# OpenModem_Schematic.net
KiCad netlist of a schematic drawn in EAGLE
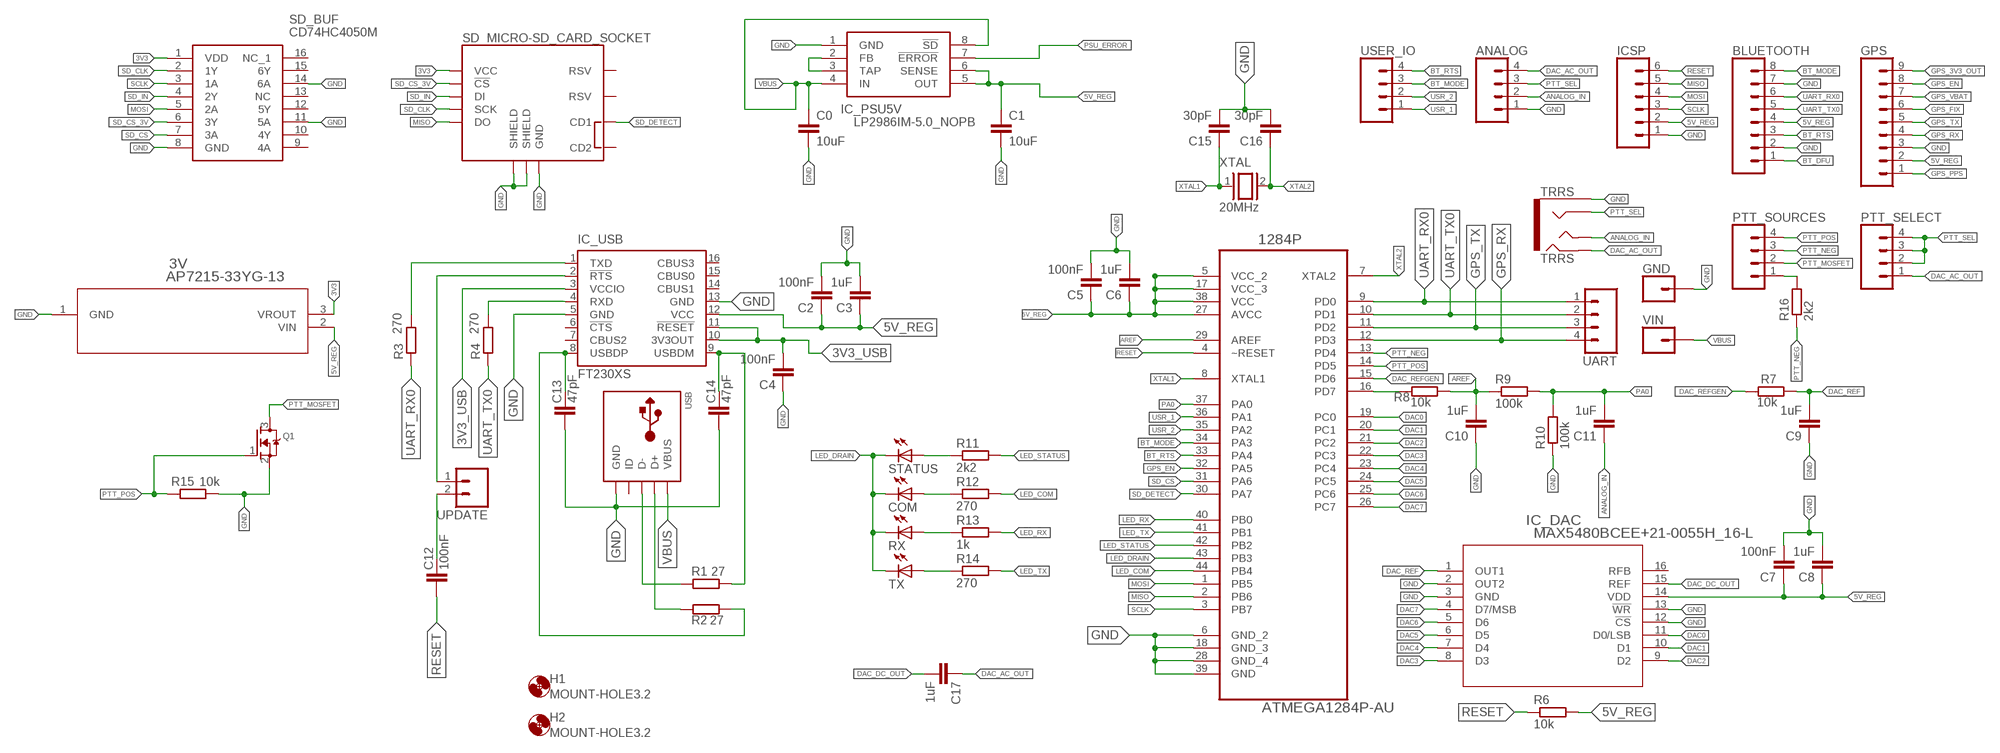
[diagram p0: schematic, sheet 1]

(export (version "E")
  (design (tool "Eeschema 10.0.6"))
  (components
    (comp (ref "3V")
      (value "AP7215-33YG-13")
      (footprint "eagle-import:SOT89-3L")
      (fields (field (name "MANUFACTURER_PART_NUMBER") "AP721533YG13"))
      (libsource (lib "eagle-import") (part "AP7215-33YG-13"))
    )
    (comp (ref "1284P")
      (value "ATMEGA1284P-AU")
      (footprint "eagle-import:QFP80P1200X1200X120-44N")
      (libsource (lib "eagle-import") (part "ATMEGA1284P-AU"))
    )
    (comp (ref "ANALOG")
      (value "CONN_04")
      (footprint "eagle-import:1X04")
      (libsource (lib "eagle-import") (part "CONN_04"))
    )
    (comp (ref "BLUETOOTH")
      (value "CONN_08\"")
      (footprint "eagle-import:1X08")
      (libsource (lib "eagle-import") (part "CONN_08{dblquote}"))
    )
    (comp (ref "C0")
      (value "10uF")
      (footprint "eagle-import:C0805")
      (libsource (lib "eagle-import") (part "C-EUC0805"))
    )
    (comp (ref "C1")
      (value "10uF")
      (footprint "eagle-import:C0805")
      (libsource (lib "eagle-import") (part "C-EUC0805"))
    )
    (comp (ref "C2")
      (value "100nF")
      (footprint "eagle-import:C0603")
      (libsource (lib "eagle-import") (part "C-EUC0603"))
    )
    (comp (ref "C3")
      (value "1uF")
      (footprint "eagle-import:C0603")
      (libsource (lib "eagle-import") (part "C-EUC0603"))
    )
    (comp (ref "C4")
      (value "100nF")
      (footprint "eagle-import:C0603")
      (libsource (lib "eagle-import") (part "C-EUC0603"))
    )
    (comp (ref "C5")
      (value "100nF")
      (footprint "eagle-import:C0603")
      (libsource (lib "eagle-import") (part "C-EUC0603"))
    )
    (comp (ref "C6")
      (value "1uF")
      (footprint "eagle-import:C0603")
      (libsource (lib "eagle-import") (part "C-EUC0603"))
    )
    (comp (ref "C7")
      (value "100nF")
      (footprint "eagle-import:C0603")
      (libsource (lib "eagle-import") (part "C-EUC0603"))
    )
    (comp (ref "C8")
      (value "1uF")
      (footprint "eagle-import:C0603")
      (libsource (lib "eagle-import") (part "C-EUC0603"))
    )
    (comp (ref "C9")
      (value "1uF")
      (footprint "eagle-import:C0603")
      (libsource (lib "eagle-import") (part "C-EUC0603"))
    )
    (comp (ref "C10")
      (value "1uF")
      (footprint "eagle-import:C0603")
      (libsource (lib "eagle-import") (part "C-EUC0603"))
    )
    (comp (ref "C11")
      (value "1uF")
      (footprint "eagle-import:C0603")
      (libsource (lib "eagle-import") (part "C-EUC0603"))
    )
    (comp (ref "C12")
      (value "100nF")
      (footprint "eagle-import:C0603")
      (libsource (lib "eagle-import") (part "C-EUC0603"))
    )
    (comp (ref "C13")
      (value "47pF")
      (footprint "eagle-import:C0603")
      (libsource (lib "eagle-import") (part "C-EUC0603"))
    )
    (comp (ref "C14")
      (value "47pF")
      (footprint "eagle-import:C0603")
      (libsource (lib "eagle-import") (part "C-EUC0603"))
    )
    (comp (ref "C15")
      (value "30pF")
      (footprint "eagle-import:C0603")
      (libsource (lib "eagle-import") (part "C-EUC0603"))
    )
    (comp (ref "C16")
      (value "30pF")
      (footprint "eagle-import:C0603")
      (libsource (lib "eagle-import") (part "C-EUC0603"))
    )
    (comp (ref "C17")
      (value "1uF")
      (footprint "eagle-import:C0603")
      (libsource (lib "eagle-import") (part "C-EUC0603"))
    )
    (comp (ref "COM")
      (value "LEDCHIP-LED0603")
      (footprint "eagle-import:CHIP-LED0603")
      (libsource (lib "eagle-import") (part "LEDCHIP-LED0603"))
    )
    (comp (ref "GND")
      (value "CONN_01")
      (footprint "eagle-import:1X01")
      (libsource (lib "eagle-import") (part "CONN_01"))
    )
    (comp (ref "GPS")
      (value "CONN_09")
      (footprint "eagle-import:1X09")
      (libsource (lib "eagle-import") (part "CONN_09"))
    )
    (comp (ref "H1")
      (value "MOUNT-HOLE3.2")
      (footprint "eagle-import:3,2")
      (libsource (lib "eagle-import") (part "MOUNT-HOLE3.2"))
    )
    (comp (ref "H2")
      (value "MOUNT-HOLE3.2")
      (footprint "eagle-import:3,2")
      (libsource (lib "eagle-import") (part "MOUNT-HOLE3.2"))
    )
    (comp (ref "ICSP")
      (value "CONN_06SILK_FEMALE_PTH")
      (footprint "eagle-import:1X06")
      (libsource (lib "eagle-import") (part "CONN_06SILK_FEMALE_PTH"))
    )
    (comp (ref "IC_DAC")
      (value "MAX5480BCEE+21-0055H_16-L")
      (footprint "eagle-import:21-0055H_16-L")
      (fields (field (name "MANUFACTURER_PART_NUMBER") "MAX5480BCEE+"))
      (libsource (lib "eagle-import") (part "MAX5480BCEE+21-0055H_16-L"))
    )
    (comp (ref "IC_PSU5V")
      (value "LP2986IM-5.0_NOPB")
      (footprint "eagle-import:SOIC127P600X175-8N")
      (fields
        (field (name "MANUFACTURER_PART_NUMBER") "LP2986IM-5.0/NOPB")
        (field (name "MOUSER_PART_NUMBER") "926-2986IM-5.0/NOPB")
      )
      (libsource (lib "eagle-import") (part "LP2986IM-5.0_NOPB"))
    )
    (comp (ref "IC_USB")
      (value "FT230XS")
      (footprint "eagle-import:SSOP16")
      (libsource (lib "eagle-import") (part "FT230XS"))
    )
    (comp (ref "PTT_SELECT")
      (value "CONN_04")
      (footprint "eagle-import:1X04")
      (libsource (lib "eagle-import") (part "CONN_04"))
    )
    (comp (ref "PTT_SOURCES")
      (value "CONN_04")
      (footprint "eagle-import:1X04")
      (libsource (lib "eagle-import") (part "CONN_04"))
    )
    (comp (ref "Q1")
      (value "MOSFET-NSMALLER")
      (footprint "eagle-import:SOT23-SMALLER")
      (libsource (lib "eagle-import") (part "MOSFET-NSMALLER"))
    )
    (comp (ref "R1")
      (value "27")
      (footprint "eagle-import:R0603")
      (libsource (lib "eagle-import") (part "R-EU_R0603"))
    )
    (comp (ref "R2")
      (value "27")
      (footprint "eagle-import:R0603")
      (libsource (lib "eagle-import") (part "R-EU_R0603"))
    )
    (comp (ref "R3")
      (value "270")
      (footprint "eagle-import:R0603")
      (libsource (lib "eagle-import") (part "R-EU_R0603"))
    )
    (comp (ref "R4")
      (value "270")
      (footprint "eagle-import:R0603")
      (libsource (lib "eagle-import") (part "R-EU_R0603"))
    )
    (comp (ref "R6")
      (value "10k")
      (footprint "eagle-import:R0603")
      (libsource (lib "eagle-import") (part "R-EU_R0603"))
    )
    (comp (ref "R7")
      (value "10k")
      (footprint "eagle-import:R0603")
      (libsource (lib "eagle-import") (part "R-EU_R0603"))
    )
    (comp (ref "R8")
      (value "10k")
      (footprint "eagle-import:R0603")
      (libsource (lib "eagle-import") (part "R-EU_R0603"))
    )
    (comp (ref "R9")
      (value "100k")
      (footprint "eagle-import:R0603")
      (libsource (lib "eagle-import") (part "R-EU_R0603"))
    )
    (comp (ref "R10")
      (value "100k")
      (footprint "eagle-import:R0603")
      (libsource (lib "eagle-import") (part "R-EU_R0603"))
    )
    (comp (ref "R11")
      (value "2k2")
      (footprint "eagle-import:R0603")
      (libsource (lib "eagle-import") (part "R-EU_R0603"))
    )
    (comp (ref "R12")
      (value "270")
      (footprint "eagle-import:R0603")
      (libsource (lib "eagle-import") (part "R-EU_R0603"))
    )
    (comp (ref "R13")
      (value "1k")
      (footprint "eagle-import:R0603")
      (libsource (lib "eagle-import") (part "R-EU_R0603"))
    )
    (comp (ref "R14")
      (value "270")
      (footprint "eagle-import:R0603")
      (libsource (lib "eagle-import") (part "R-EU_R0603"))
    )
    (comp (ref "R15")
      (value "10k")
      (footprint "eagle-import:R0603")
      (libsource (lib "eagle-import") (part "R-EU_R0603"))
    )
    (comp (ref "R16")
      (value "2k2")
      (footprint "eagle-import:R0603")
      (libsource (lib "eagle-import") (part "R-EU_R0603"))
    )
    (comp (ref "RX")
      (value "LEDCHIP-LED0603")
      (footprint "eagle-import:CHIP-LED0603")
      (libsource (lib "eagle-import") (part "LEDCHIP-LED0603"))
    )
    (comp (ref "SD")
      (value "MICRO-SD_CARD_SOCKET")
      (footprint "eagle-import:MICRO-SD-SOCKET")
      (libsource (lib "eagle-import") (part "MICRO-SD_CARD_SOCKET"))
    )
    (comp (ref "SD_BUF")
      (value "CD74HC4050M")
      (footprint "eagle-import:SOIC127P600X175-16N")
      (fields (field (name "MOUSER_PART_NUMBER") "595-CD74HC4050M"))
      (libsource (lib "eagle-import") (part "CD74HC4050M"))
    )
    (comp (ref "STATUS")
      (value "LEDCHIP-LED0603")
      (footprint "eagle-import:CHIP-LED0603")
      (libsource (lib "eagle-import") (part "LEDCHIP-LED0603"))
    )
    (comp (ref "TRRS")
      (value "TRRS")
      (footprint "eagle-import:AUDIO_JACK_3.5MM_TRRS_SMD_RA")
      (libsource (lib "eagle-import") (part "AUDIO_JACK_TRRSSMD_RA"))
    )
    (comp (ref "TX")
      (value "LEDCHIP-LED0603")
      (footprint "eagle-import:CHIP-LED0603")
      (libsource (lib "eagle-import") (part "LEDCHIP-LED0603"))
    )
    (comp (ref "UART")
      (value "M04PTH")
      (footprint "eagle-import:1X04")
      (libsource (lib "eagle-import") (part "M04PTH"))
    )
    (comp (ref "UPDATE")
      (value "M02PTH")
      (footprint "eagle-import:1X02")
      (libsource (lib "eagle-import") (part "M02PTH"))
    )
    (comp (ref "USB")
      (value "USBMOLEX")
      (footprint "eagle-import:USB-MINIB-THM-MOLEX")
      (libsource (lib "eagle-import") (part "USBMOLEX"))
    )
    (comp (ref "USER_IO")
      (value "CONN_04")
      (footprint "eagle-import:1X04")
      (libsource (lib "eagle-import") (part "CONN_04"))
    )
    (comp (ref "VIN")
      (value "CONN_01")
      (footprint "eagle-import:1X01")
      (libsource (lib "eagle-import") (part "CONN_01"))
    )
    (comp (ref "XTAL")
      (value "20MHz")
      (footprint "eagle-import:QS")
      (libsource (lib "eagle-import") (part "XTAL/S"))
    )
  )
  (nets
    (net (code "1") (name "3V3") (class "Default")
      (node (ref "3V") (pin "3") (pinfunction "VROUT_3") (pintype "output"))
      (node (ref "SD") (pin "VCC") (pinfunction "VCC_VCC") (pintype "bidirectional"))
      (node (ref "SD_BUF") (pin "1") (pinfunction "VDD_1") (pintype "power_in"))
    )
    (net (code "2") (name "3V3_USB") (class "Default")
      (node (ref "C4") (pin "2") (pinfunction "2_2") (pintype "passive"))
      (node (ref "IC_USB") (pin "10") (pinfunction "3V3OUT_10") (pintype "output"))
      (node (ref "IC_USB") (pin "11") (pinfunction "~{RESET}_11") (pintype "input"))
      (node (ref "IC_USB") (pin "3") (pinfunction "VCCIO_3") (pintype "power_in"))
    )
    (net (code "3") (name "5V_REG") (class "Default")
      (node (ref "1284P") (pin "17") (pinfunction "VCC_3_17") (pintype "power_in"))
      (node (ref "1284P") (pin "27") (pinfunction "AVCC_27") (pintype "power_in"))
      (node (ref "1284P") (pin "38") (pinfunction "VCC_38") (pintype "power_in"))
      (node (ref "1284P") (pin "5") (pinfunction "VCC_2_5") (pintype "power_in"))
      (node (ref "3V") (pin "2") (pinfunction "VIN_2") (pintype "input"))
      (node (ref "BLUETOOTH") (pin "4") (pinfunction "4_4") (pintype "passive"))
      (node (ref "C1") (pin "1") (pinfunction "1_1") (pintype "passive"))
      (node (ref "C2") (pin "1") (pinfunction "1_1") (pintype "passive"))
      (node (ref "C3") (pin "1") (pinfunction "1_1") (pintype "passive"))
      (node (ref "C5") (pin "1") (pinfunction "1_1") (pintype "passive"))
      (node (ref "C6") (pin "1") (pinfunction "1_1") (pintype "passive"))
      (node (ref "C7") (pin "1") (pinfunction "1_1") (pintype "passive"))
      (node (ref "C8") (pin "1") (pinfunction "1_1") (pintype "passive"))
      (node (ref "GPS") (pin "2") (pinfunction "2_2") (pintype "passive"))
      (node (ref "ICSP") (pin "2") (pinfunction "2_2") (pintype "passive"))
      (node (ref "IC_DAC") (pin "14") (pinfunction "VDD_14") (pintype "power_in"))
      (node (ref "IC_PSU5V") (pin "5") (pinfunction "OUT_5") (pintype "output"))
      (node (ref "IC_PSU5V") (pin "6") (pinfunction "SENSE_6") (pintype "bidirectional"))
      (node (ref "IC_USB") (pin "12") (pinfunction "VCC_12") (pintype "power_in"))
      (node (ref "R6") (pin "2") (pinfunction "2_2") (pintype "passive"))
    )
    (net (code "4") (name "ANALOG_IN") (class "Default")
      (node (ref "ANALOG") (pin "2") (pinfunction "2_2") (pintype "passive"))
      (node (ref "C11") (pin "1") (pinfunction "1_1") (pintype "passive"))
      (node (ref "TRRS") (pin "TIP") (pinfunction "TIP_TIP") (pintype "bidirectional"))
    )
    (net (code "5") (name "AREF") (class "Default")
      (node (ref "1284P") (pin "29") (pinfunction "AREF_29") (pintype "input"))
      (node (ref "C10") (pin "2") (pinfunction "2_2") (pintype "passive"))
      (node (ref "R8") (pin "2") (pinfunction "2_2") (pintype "passive"))
      (node (ref "R9") (pin "1") (pinfunction "1_1") (pintype "passive"))
    )
    (net (code "6") (name "BT_DFU") (class "Default")
      (node (ref "BLUETOOTH") (pin "1") (pinfunction "1_1") (pintype "passive"))
    )
    (net (code "7") (name "BT_MODE") (class "Default")
      (node (ref "1284P") (pin "34") (pinfunction "PA3_34") (pintype "bidirectional"))
      (node (ref "BLUETOOTH") (pin "8") (pinfunction "8_8") (pintype "passive"))
      (node (ref "USER_IO") (pin "3") (pinfunction "3_3") (pintype "passive"))
    )
    (net (code "8") (name "BT_RTS") (class "Default")
      (node (ref "1284P") (pin "33") (pinfunction "PA4_33") (pintype "bidirectional"))
      (node (ref "BLUETOOTH") (pin "3") (pinfunction "3_3") (pintype "passive"))
      (node (ref "USER_IO") (pin "4") (pinfunction "4_4") (pintype "passive"))
    )
    (net (code "9") (name "DAC0") (class "Default")
      (node (ref "1284P") (pin "19") (pinfunction "PC0_19") (pintype "bidirectional"))
      (node (ref "IC_DAC") (pin "11") (pinfunction "D0/LSB_11") (pintype "input"))
    )
    (net (code "10") (name "DAC1") (class "Default")
      (node (ref "1284P") (pin "20") (pinfunction "PC1_20") (pintype "bidirectional"))
      (node (ref "IC_DAC") (pin "10") (pinfunction "D1_10") (pintype "input"))
    )
    (net (code "11") (name "DAC2") (class "Default")
      (node (ref "1284P") (pin "21") (pinfunction "PC2_21") (pintype "bidirectional"))
      (node (ref "IC_DAC") (pin "9") (pinfunction "D2_9") (pintype "input"))
    )
    (net (code "12") (name "DAC3") (class "Default")
      (node (ref "1284P") (pin "22") (pinfunction "PC3_22") (pintype "bidirectional"))
      (node (ref "IC_DAC") (pin "8") (pinfunction "D3_8") (pintype "input"))
    )
    (net (code "13") (name "DAC4") (class "Default")
      (node (ref "1284P") (pin "23") (pinfunction "PC4_23") (pintype "bidirectional"))
      (node (ref "IC_DAC") (pin "7") (pinfunction "D4_7") (pintype "input"))
    )
    (net (code "14") (name "DAC5") (class "Default")
      (node (ref "1284P") (pin "24") (pinfunction "PC5_24") (pintype "bidirectional"))
      (node (ref "IC_DAC") (pin "6") (pinfunction "D5_6") (pintype "input"))
    )
    (net (code "15") (name "DAC6") (class "Default")
      (node (ref "1284P") (pin "25") (pinfunction "PC6_25") (pintype "bidirectional"))
      (node (ref "IC_DAC") (pin "5") (pinfunction "D6_5") (pintype "input"))
    )
    (net (code "16") (name "DAC7") (class "Default")
      (node (ref "1284P") (pin "26") (pinfunction "PC7_26") (pintype "bidirectional"))
      (node (ref "IC_DAC") (pin "4") (pinfunction "D7/MSB_4") (pintype "input"))
    )
    (net (code "17") (name "DAC_AC_OUT") (class "Default")
      (node (ref "ANALOG") (pin "4") (pinfunction "4_4") (pintype "passive"))
      (node (ref "C17") (pin "1") (pinfunction "1_1") (pintype "passive"))
      (node (ref "PTT_SELECT") (pin "1") (pinfunction "1_1") (pintype "passive"))
      (node (ref "TRRS") (pin "RING2") (pinfunction "RING2_RING2") (pintype "bidirectional"))
    )
    (net (code "18") (name "DAC_DC_OUT") (class "Default")
      (node (ref "C17") (pin "2") (pinfunction "2_2") (pintype "passive"))
      (node (ref "IC_DAC") (pin "15") (pinfunction "REF_15") (pintype "input"))
    )
    (net (code "19") (name "DAC_REF") (class "Default")
      (node (ref "C9") (pin "2") (pinfunction "2_2") (pintype "passive"))
      (node (ref "IC_DAC") (pin "1") (pinfunction "OUT1_1") (pintype "output"))
      (node (ref "R7") (pin "2") (pinfunction "2_2") (pintype "passive"))
    )
    (net (code "20") (name "DAC_REFGEN") (class "Default")
      (node (ref "1284P") (pin "15") (pinfunction "PD6_15") (pintype "bidirectional"))
      (node (ref "R7") (pin "1") (pinfunction "1_1") (pintype "passive"))
    )
    (net (code "21") (name "GND") (class "Default")
      (node (ref "1284P") (pin "18") (pinfunction "GND_3_18") (pintype "passive"))
      (node (ref "1284P") (pin "28") (pinfunction "GND_4_28") (pintype "passive"))
      (node (ref "1284P") (pin "39") (pinfunction "GND_39") (pintype "passive"))
      (node (ref "1284P") (pin "6") (pinfunction "GND_2_6") (pintype "passive"))
      (node (ref "3V") (pin "1") (pinfunction "GND_1") (pintype "power_in"))
      (node (ref "ANALOG") (pin "1") (pinfunction "1_1") (pintype "passive"))
      (node (ref "BLUETOOTH") (pin "2") (pinfunction "2_2") (pintype "passive"))
      (node (ref "BLUETOOTH") (pin "7") (pinfunction "7_7") (pintype "passive"))
      (node (ref "C0") (pin "2") (pinfunction "2_2") (pintype "passive"))
      (node (ref "C1") (pin "2") (pinfunction "2_2") (pintype "passive"))
      (node (ref "C10") (pin "1") (pinfunction "1_1") (pintype "passive"))
      (node (ref "C13") (pin "1") (pinfunction "1_1") (pintype "passive"))
      (node (ref "C14") (pin "1") (pinfunction "1_1") (pintype "passive"))
      (node (ref "C15") (pin "2") (pinfunction "2_2") (pintype "passive"))
      (node (ref "C16") (pin "2") (pinfunction "2_2") (pintype "passive"))
      (node (ref "C2") (pin "2") (pinfunction "2_2") (pintype "passive"))
      (node (ref "C3") (pin "2") (pinfunction "2_2") (pintype "passive"))
      (node (ref "C4") (pin "1") (pinfunction "1_1") (pintype "passive"))
      (node (ref "C5") (pin "2") (pinfunction "2_2") (pintype "passive"))
      (node (ref "C6") (pin "2") (pinfunction "2_2") (pintype "passive"))
      (node (ref "C7") (pin "2") (pinfunction "2_2") (pintype "passive"))
      (node (ref "C8") (pin "2") (pinfunction "2_2") (pintype "passive"))
      (node (ref "C9") (pin "1") (pinfunction "1_1") (pintype "passive"))
      (node (ref "GND") (pin "1") (pinfunction "1_1") (pintype "passive"))
      (node (ref "GPS") (pin "3") (pinfunction "3_3") (pintype "passive"))
      (node (ref "ICSP") (pin "1") (pinfunction "1_1") (pintype "passive"))
      (node (ref "IC_DAC") (pin "12") (pinfunction "~{CS}_12") (pintype "input"))
      (node (ref "IC_DAC") (pin "13") (pinfunction "~{WR}_13") (pintype "input"))
      (node (ref "IC_DAC") (pin "2") (pinfunction "OUT2_2") (pintype "output"))
      (node (ref "IC_DAC") (pin "3") (pinfunction "GND_3") (pintype "power_in"))
      (node (ref "IC_PSU5V") (pin "1") (pinfunction "GND_1") (pintype "power_in"))
      (node (ref "IC_USB") (pin "13") (pinfunction "GND_13") (pintype "power_in"))
      (node (ref "IC_USB") (pin "5") (pinfunction "GND_5") (pintype "power_in"))
      (node (ref "Q1") (pin "2") (pinfunction "S_2") (pintype "bidirectional"))
      (node (ref "R10") (pin "1") (pinfunction "1_1") (pintype "passive"))
      (node (ref "R15") (pin "1") (pinfunction "1_1") (pintype "passive"))
      (node (ref "SD") (pin "GND") (pinfunction "GND_GND") (pintype "bidirectional"))
      (node (ref "SD") (pin "GND1") (pinfunction "SHIELD_GND1") (pintype "bidirectional"))
      (node (ref "SD") (pin "GND3") (pinfunction "SHIELD_GND3") (pintype "bidirectional"))
      (node (ref "SD_BUF") (pin "11") (pinfunction "5A_11") (pintype "bidirectional"))
      (node (ref "SD_BUF") (pin "14") (pinfunction "6A_14") (pintype "bidirectional"))
      (node (ref "SD_BUF") (pin "8") (pinfunction "GND_8") (pintype "power_in"))
      (node (ref "TRRS") (pin "EARTH") (pinfunction "EARTH_EARTH") (pintype "bidirectional"))
      (node (ref "USB") (pin "GND") (pinfunction "GND_GND") (pintype "power_in"))
    )
    (net (code "22") (name "GPS_3V3_OUT") (class "Default")
      (node (ref "GPS") (pin "9") (pinfunction "9_9") (pintype "passive"))
    )
    (net (code "23") (name "GPS_EN") (class "Default")
      (node (ref "1284P") (pin "32") (pinfunction "PA5_32") (pintype "bidirectional"))
      (node (ref "GPS") (pin "8") (pinfunction "8_8") (pintype "passive"))
    )
    (net (code "24") (name "GPS_FIX") (class "Default")
      (node (ref "GPS") (pin "6") (pinfunction "6_6") (pintype "passive"))
    )
    (net (code "25") (name "GPS_PPS") (class "Default")
      (node (ref "GPS") (pin "1") (pinfunction "1_1") (pintype "passive"))
    )
    (net (code "26") (name "GPS_RX") (class "Default")
      (node (ref "1284P") (pin "12") (pinfunction "PD3_12") (pintype "bidirectional"))
      (node (ref "GPS") (pin "4") (pinfunction "4_4") (pintype "passive"))
      (node (ref "UART") (pin "4") (pinfunction "4_4") (pintype "passive"))
    )
    (net (code "27") (name "GPS_TX") (class "Default")
      (node (ref "1284P") (pin "11") (pinfunction "PD2_11") (pintype "bidirectional"))
      (node (ref "GPS") (pin "5") (pinfunction "5_5") (pintype "passive"))
      (node (ref "UART") (pin "3") (pinfunction "3_3") (pintype "passive"))
    )
    (net (code "28") (name "GPS_VBAT") (class "Default")
      (node (ref "GPS") (pin "7") (pinfunction "7_7") (pintype "passive"))
    )
    (net (code "29") (name "LED_COM") (class "Default")
      (node (ref "1284P") (pin "44") (pinfunction "PB4_44") (pintype "bidirectional"))
      (node (ref "R12") (pin "2") (pinfunction "2_2") (pintype "passive"))
    )
    (net (code "30") (name "LED_DRAIN") (class "Default")
      (node (ref "1284P") (pin "43") (pinfunction "PB3_43") (pintype "bidirectional"))
      (node (ref "COM") (pin "C") (pinfunction "C_C") (pintype "passive"))
      (node (ref "RX") (pin "C") (pinfunction "C_C") (pintype "passive"))
      (node (ref "STATUS") (pin "C") (pinfunction "C_C") (pintype "passive"))
      (node (ref "TX") (pin "C") (pinfunction "C_C") (pintype "passive"))
    )
    (net (code "31") (name "LED_RX") (class "Default")
      (node (ref "1284P") (pin "40") (pinfunction "PB0_40") (pintype "bidirectional"))
      (node (ref "R13") (pin "2") (pinfunction "2_2") (pintype "passive"))
    )
    (net (code "32") (name "LED_STATUS") (class "Default")
      (node (ref "1284P") (pin "42") (pinfunction "PB2_42") (pintype "bidirectional"))
      (node (ref "R11") (pin "2") (pinfunction "2_2") (pintype "passive"))
    )
    (net (code "33") (name "LED_TX") (class "Default")
      (node (ref "1284P") (pin "41") (pinfunction "PB1_41") (pintype "bidirectional"))
      (node (ref "R14") (pin "2") (pinfunction "2_2") (pintype "passive"))
    )
    (net (code "34") (name "MISO") (class "Default")
      (node (ref "1284P") (pin "2") (pinfunction "PB6_2") (pintype "bidirectional"))
      (node (ref "ICSP") (pin "5") (pinfunction "5_5") (pintype "passive"))
      (node (ref "SD") (pin "DO") (pinfunction "DO_DO") (pintype "bidirectional"))
    )
    (net (code "35") (name "MOSI") (class "Default")
      (node (ref "1284P") (pin "1") (pinfunction "PB5_1") (pintype "bidirectional"))
      (node (ref "ICSP") (pin "4") (pinfunction "4_4") (pintype "passive"))
      (node (ref "SD_BUF") (pin "5") (pinfunction "2A_5") (pintype "bidirectional"))
    )
    (net (code "36") (name "Net-(1284P-PD7)") (class "Default")
      (node (ref "1284P") (pin "16") (pinfunction "PD7_16") (pintype "bidirectional"))
      (node (ref "R8") (pin "1") (pinfunction "1_1") (pintype "passive"))
    )
    (net (code "37") (name "Net-(C12-Pad2)") (class "Default")
      (node (ref "C12") (pin "2") (pinfunction "2_2") (pintype "passive"))
      (node (ref "UPDATE") (pin "2") (pinfunction "2_2") (pintype "passive"))
    )
    (net (code "38") (name "Net-(COM-PadA)") (class "Default")
      (node (ref "COM") (pin "A") (pinfunction "A_A") (pintype "passive"))
      (node (ref "R12") (pin "1") (pinfunction "1_1") (pintype "passive"))
    )
    (net (code "39") (name "Net-(IC_PSU5V-FB)") (class "Default")
      (node (ref "IC_PSU5V") (pin "2") (pinfunction "FB_2") (pintype "bidirectional"))
      (node (ref "IC_PSU5V") (pin "3") (pinfunction "TAP_3") (pintype "bidirectional"))
    )
    (net (code "40") (name "Net-(IC_USB-RXD)") (class "Default")
      (node (ref "IC_USB") (pin "4") (pinfunction "RXD_4") (pintype "input"))
      (node (ref "R4") (pin "2") (pinfunction "2_2") (pintype "passive"))
    )
    (net (code "41") (name "Net-(IC_USB-TXD)") (class "Default")
      (node (ref "IC_USB") (pin "1") (pinfunction "TXD_1") (pintype "output"))
      (node (ref "R3") (pin "2") (pinfunction "2_2") (pintype "passive"))
    )
    (net (code "42") (name "Net-(IC_USB-USBDM)") (class "Default")
      (node (ref "C14") (pin "2") (pinfunction "2_2") (pintype "passive"))
      (node (ref "IC_USB") (pin "9") (pinfunction "USBDM_9") (pintype "input"))
      (node (ref "R1") (pin "1") (pinfunction "1_1") (pintype "passive"))
    )
    (net (code "43") (name "Net-(IC_USB-USBDP)") (class "Default")
      (node (ref "C13") (pin "2") (pinfunction "2_2") (pintype "passive"))
      (node (ref "IC_USB") (pin "8") (pinfunction "USBDP_8") (pintype "input"))
      (node (ref "R2") (pin "1") (pinfunction "1_1") (pintype "passive"))
    )
    (net (code "44") (name "Net-(IC_USB-~{RTS})") (class "Default")
      (node (ref "IC_USB") (pin "2") (pinfunction "~{RTS}_2") (pintype "output"))
      (node (ref "UPDATE") (pin "1") (pinfunction "1_1") (pintype "passive"))
    )
    (net (code "45") (name "Net-(PTT_SOURCES-Pad1)") (class "Default")
      (node (ref "PTT_SOURCES") (pin "1") (pinfunction "1_1") (pintype "passive"))
      (node (ref "R16") (pin "2") (pinfunction "2_2") (pintype "passive"))
    )
    (net (code "46") (name "Net-(R1-Pad2)") (class "Default")
      (node (ref "R1") (pin "2") (pinfunction "2_2") (pintype "passive"))
      (node (ref "USB") (pin "D-") (pinfunction "D-_D-") (pintype "bidirectional"))
    )
    (net (code "47") (name "Net-(R2-Pad2)") (class "Default")
      (node (ref "R2") (pin "2") (pinfunction "2_2") (pintype "passive"))
      (node (ref "USB") (pin "D+") (pinfunction "D+_D+") (pintype "bidirectional"))
    )
    (net (code "48") (name "Net-(R11-Pad1)") (class "Default")
      (node (ref "R11") (pin "1") (pinfunction "1_1") (pintype "passive"))
      (node (ref "STATUS") (pin "A") (pinfunction "A_A") (pintype "passive"))
    )
    (net (code "49") (name "Net-(R13-Pad1)") (class "Default")
      (node (ref "R13") (pin "1") (pinfunction "1_1") (pintype "passive"))
      (node (ref "RX") (pin "A") (pinfunction "A_A") (pintype "passive"))
    )
    (net (code "50") (name "Net-(R14-Pad1)") (class "Default")
      (node (ref "R14") (pin "1") (pinfunction "1_1") (pintype "passive"))
      (node (ref "TX") (pin "A") (pinfunction "A_A") (pintype "passive"))
    )
    (net (code "51") (name "PA0") (class "Default")
      (node (ref "1284P") (pin "37") (pinfunction "PA0_37") (pintype "bidirectional"))
      (node (ref "C11") (pin "2") (pinfunction "2_2") (pintype "passive"))
      (node (ref "R10") (pin "2") (pinfunction "2_2") (pintype "passive"))
      (node (ref "R9") (pin "2") (pinfunction "2_2") (pintype "passive"))
    )
    (net (code "52") (name "PSU_ERROR") (class "Default")
      (node (ref "IC_PSU5V") (pin "7") (pinfunction "~{ERROR}_7") (pintype "bidirectional"))
    )
    (net (code "53") (name "PTT_MOSFET") (class "Default")
      (node (ref "PTT_SOURCES") (pin "2") (pinfunction "2_2") (pintype "passive"))
      (node (ref "Q1") (pin "3") (pinfunction "D_3") (pintype "bidirectional"))
    )
    (net (code "54") (name "PTT_NEG") (class "Default")
      (node (ref "1284P") (pin "13") (pinfunction "PD4_13") (pintype "bidirectional"))
      (node (ref "PTT_SOURCES") (pin "3") (pinfunction "3_3") (pintype "passive"))
      (node (ref "R16") (pin "1") (pinfunction "1_1") (pintype "passive"))
    )
    (net (code "55") (name "PTT_POS") (class "Default")
      (node (ref "1284P") (pin "14") (pinfunction "PD5_14") (pintype "bidirectional"))
      (node (ref "PTT_SOURCES") (pin "4") (pinfunction "4_4") (pintype "passive"))
      (node (ref "Q1") (pin "1") (pinfunction "G_1") (pintype "bidirectional"))
      (node (ref "R15") (pin "2") (pinfunction "2_2") (pintype "passive"))
    )
    (net (code "56") (name "PTT_SEL") (class "Default")
      (node (ref "ANALOG") (pin "3") (pinfunction "3_3") (pintype "passive"))
      (node (ref "PTT_SELECT") (pin "2") (pinfunction "2_2") (pintype "passive"))
      (node (ref "PTT_SELECT") (pin "3") (pinfunction "3_3") (pintype "passive"))
      (node (ref "PTT_SELECT") (pin "4") (pinfunction "4_4") (pintype "passive"))
      (node (ref "TRRS") (pin "RING1") (pinfunction "RING1_RING1") (pintype "bidirectional"))
    )
    (net (code "57") (name "RESET") (class "Default")
      (node (ref "1284P") (pin "4") (pinfunction "~{RESET}_4") (pintype "input"))
      (node (ref "C12") (pin "1") (pinfunction "1_1") (pintype "passive"))
      (node (ref "ICSP") (pin "6") (pinfunction "6_6") (pintype "passive"))
      (node (ref "R6") (pin "1") (pinfunction "1_1") (pintype "passive"))
    )
    (net (code "58") (name "SCLK") (class "Default")
      (node (ref "1284P") (pin "3") (pinfunction "PB7_3") (pintype "bidirectional"))
      (node (ref "ICSP") (pin "3") (pinfunction "3_3") (pintype "passive"))
      (node (ref "SD_BUF") (pin "3") (pinfunction "1A_3") (pintype "bidirectional"))
    )
    (net (code "59") (name "SD_CLK") (class "Default")
      (node (ref "SD") (pin "SCLK") (pinfunction "SCK_SCLK") (pintype "bidirectional"))
      (node (ref "SD_BUF") (pin "2") (pinfunction "1Y_2") (pintype "bidirectional"))
    )
    (net (code "60") (name "SD_CS") (class "Default")
      (node (ref "1284P") (pin "31") (pinfunction "PA6_31") (pintype "bidirectional"))
      (node (ref "SD_BUF") (pin "7") (pinfunction "3A_7") (pintype "bidirectional"))
    )
    (net (code "61") (name "SD_CS_3V") (class "Default")
      (node (ref "SD") (pin "CS") (pinfunction "~{CS}_CS") (pintype "bidirectional"))
      (node (ref "SD_BUF") (pin "6") (pinfunction "3Y_6") (pintype "bidirectional"))
    )
    (net (code "62") (name "SD_DETECT") (class "Default")
      (node (ref "1284P") (pin "30") (pinfunction "PA7_30") (pintype "bidirectional"))
      (node (ref "SD") (pin "CD1") (pinfunction "CD1_CD1") (pintype "bidirectional"))
    )
    (net (code "63") (name "SD_IN") (class "Default")
      (node (ref "SD") (pin "DI") (pinfunction "DI_DI") (pintype "bidirectional"))
      (node (ref "SD_BUF") (pin "4") (pinfunction "2Y_4") (pintype "bidirectional"))
    )
    (net (code "64") (name "UART_RX0") (class "Default")
      (node (ref "1284P") (pin "9") (pinfunction "PD0_9") (pintype "bidirectional"))
      (node (ref "BLUETOOTH") (pin "6") (pinfunction "6_6") (pintype "passive"))
      (node (ref "R3") (pin "1") (pinfunction "1_1") (pintype "passive"))
      (node (ref "UART") (pin "1") (pinfunction "1_1") (pintype "passive"))
    )
    (net (code "65") (name "UART_TX0") (class "Default")
      (node (ref "1284P") (pin "10") (pinfunction "PD1_10") (pintype "bidirectional"))
      (node (ref "BLUETOOTH") (pin "5") (pinfunction "5_5") (pintype "passive"))
      (node (ref "R4") (pin "1") (pinfunction "1_1") (pintype "passive"))
      (node (ref "UART") (pin "2") (pinfunction "2_2") (pintype "passive"))
    )
    (net (code "66") (name "USR_1") (class "Default")
      (node (ref "1284P") (pin "36") (pinfunction "PA1_36") (pintype "bidirectional"))
      (node (ref "USER_IO") (pin "1") (pinfunction "1_1") (pintype "passive"))
    )
    (net (code "67") (name "USR_2") (class "Default")
      (node (ref "1284P") (pin "35") (pinfunction "PA2_35") (pintype "bidirectional"))
      (node (ref "USER_IO") (pin "2") (pinfunction "2_2") (pintype "passive"))
    )
    (net (code "68") (name "VBUS") (class "Default")
      (node (ref "C0") (pin "1") (pinfunction "1_1") (pintype "passive"))
      (node (ref "IC_PSU5V") (pin "4") (pinfunction "IN_4") (pintype "input"))
      (node (ref "IC_PSU5V") (pin "8") (pinfunction "~{SD}_8") (pintype "bidirectional"))
      (node (ref "USB") (pin "VBUS") (pinfunction "VBUS_VBUS") (pintype "power_in"))
      (node (ref "VIN") (pin "1") (pinfunction "1_1") (pintype "passive"))
    )
    (net (code "69") (name "XTAL1") (class "Default")
      (node (ref "1284P") (pin "8") (pinfunction "XTAL1_8") (pintype "input"))
      (node (ref "C15") (pin "1") (pinfunction "1_1") (pintype "passive"))
      (node (ref "XTAL") (pin "1") (pinfunction "1_1") (pintype "passive"))
    )
    (net (code "70") (name "XTAL2") (class "Default")
      (node (ref "1284P") (pin "7") (pinfunction "XTAL2_7") (pintype "output"))
      (node (ref "C16") (pin "1") (pinfunction "1_1") (pintype "passive"))
      (node (ref "XTAL") (pin "2") (pinfunction "2_2") (pintype "passive"))
    )
    (net (code "71") (name "unconnected-(IC_DAC-RFB-Pad16)") (class "Default")
      (node (ref "IC_DAC") (pin "16") (pinfunction "RFB_16") (pintype "passive"))
    )
    (net (code "72") (name "unconnected-(IC_USB-CBUS0-Pad15)") (class "Default")
      (node (ref "IC_USB") (pin "15") (pinfunction "CBUS0_15") (pintype "bidirectional"))
    )
    (net (code "73") (name "unconnected-(IC_USB-CBUS1-Pad14)") (class "Default")
      (node (ref "IC_USB") (pin "14") (pinfunction "CBUS1_14") (pintype "bidirectional"))
    )
    (net (code "74") (name "unconnected-(IC_USB-CBUS2-Pad7)") (class "Default")
      (node (ref "IC_USB") (pin "7") (pinfunction "CBUS2_7") (pintype "bidirectional"))
    )
    (net (code "75") (name "unconnected-(IC_USB-CBUS3-Pad16)") (class "Default")
      (node (ref "IC_USB") (pin "16") (pinfunction "CBUS3_16") (pintype "bidirectional"))
    )
    (net (code "76") (name "unconnected-(IC_USB-~{CTS}-Pad6)") (class "Default")
      (node (ref "IC_USB") (pin "6") (pinfunction "~{CTS}_6") (pintype "input"))
    )
    (net (code "77") (name "unconnected-(SD-PadCD2)") (class "Default")
      (node (ref "SD") (pin "CD2") (pinfunction "CD2_CD2") (pintype "bidirectional"))
    )
    (net (code "78") (name "unconnected-(SD-RSV-PadRSV1)") (class "Default")
      (node (ref "SD") (pin "RSV1") (pinfunction "RSV_RSV1") (pintype "bidirectional"))
    )
    (net (code "79") (name "unconnected-(SD-RSV-PadRSV2)") (class "Default")
      (node (ref "SD") (pin "RSV2") (pinfunction "RSV_RSV2") (pintype "bidirectional"))
    )
    (net (code "80") (name "unconnected-(SD_BUF-4A-Pad9)") (class "Default")
      (node (ref "SD_BUF") (pin "9") (pinfunction "4A_9") (pintype "bidirectional"))
    )
    (net (code "81") (name "unconnected-(SD_BUF-4Y-Pad10)") (class "Default")
      (node (ref "SD_BUF") (pin "10") (pinfunction "4Y_10") (pintype "bidirectional"))
    )
    (net (code "82") (name "unconnected-(SD_BUF-5Y-Pad12)") (class "Default")
      (node (ref "SD_BUF") (pin "12") (pinfunction "5Y_12") (pintype "bidirectional"))
    )
    (net (code "83") (name "unconnected-(SD_BUF-6Y-Pad15)") (class "Default")
      (node (ref "SD_BUF") (pin "15") (pinfunction "6Y_15") (pintype "bidirectional"))
    )
    (net (code "84") (name "unconnected-(SD_BUF-NC-Pad13)") (class "Default")
      (node (ref "SD_BUF") (pin "13") (pinfunction "NC_13") (pintype "no_connect"))
    )
    (net (code "85") (name "unconnected-(SD_BUF-NC_1-Pad16)") (class "Default")
      (node (ref "SD_BUF") (pin "16") (pinfunction "NC_1_16") (pintype "bidirectional"))
    )
    (net (code "86") (name "unconnected-(USB-PadID)") (class "Default")
      (node (ref "USB") (pin "ID") (pinfunction "ID_ID") (pintype "bidirectional"))
    )
  )
)
